# 238_power_measure.net
KiCad netlist of a schematic drawn in EAGLE
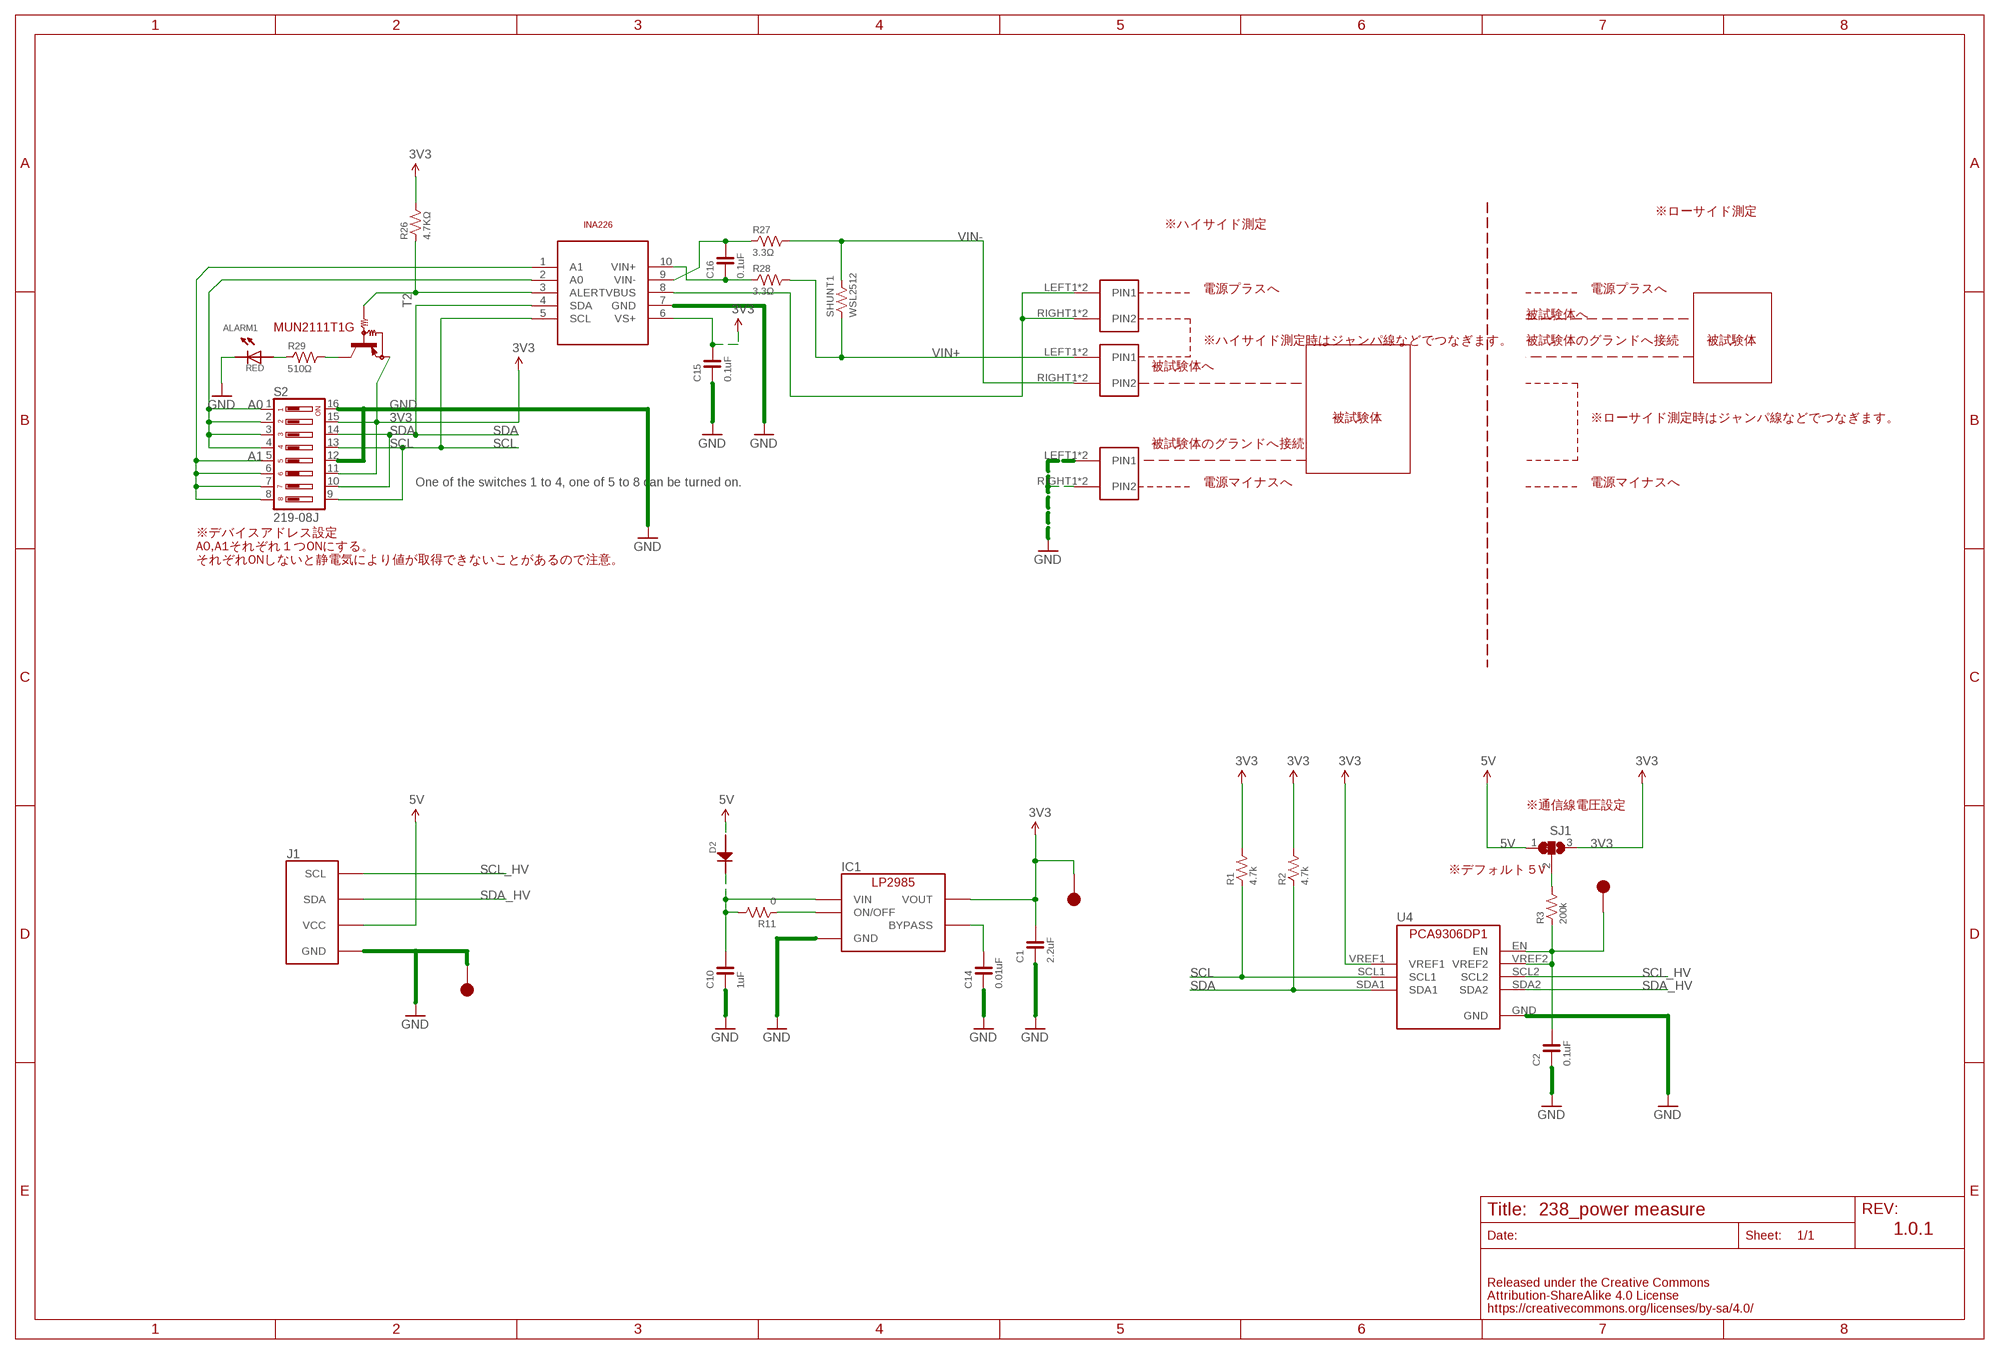
[diagram p0: schematic, sheet 1]

(export (version "E")
  (design (tool "Eeschema 10.0.6"))
  (components
    (comp (ref "ALARM1")
      (value "RED")
      (footprint "eagle-import:0603")
      (libsource (lib "eagle-import") (part "LED-0603"))
    )
    (comp (ref "C1")
      (value "2.2uF")
      (footprint "eagle-import:0603")
      (libsource (lib "eagle-import") (part "CAPACITOR-0603"))
    )
    (comp (ref "C2")
      (value "0.1uF")
      (footprint "eagle-import:0603")
      (libsource (lib "eagle-import") (part "CAPACITOR-0603"))
    )
    (comp (ref "C10")
      (value "1uF")
      (footprint "eagle-import:0603")
      (libsource (lib "eagle-import") (part "CAPACITOR-0603"))
    )
    (comp (ref "C14")
      (value "0.01uF")
      (footprint "eagle-import:0603")
      (libsource (lib "eagle-import") (part "CAPACITOR-0603"))
    )
    (comp (ref "C15")
      (value "0.1uF")
      (footprint "eagle-import:0603")
      (libsource (lib "eagle-import") (part "CAPACITOR-0603"))
    )
    (comp (ref "C16")
      (value "0.1uF")
      (footprint "eagle-import:0603")
      (libsource (lib "eagle-import") (part "CAPACITOR-0603"))
    )
    (comp (ref "D2")
      (value "1N4148")
      (footprint "eagle-import:1N4148W")
      (libsource (lib "eagle-import") (part "1N4148"))
    )
    (comp (ref "IC1")
      (value "LP2985-33")
      (footprint "eagle-import:SOT-23-5")
      (libsource (lib "eagle-import") (part "LP2985-33DBV"))
    )
    (comp (ref "J1")
      (value "FABO_BRICK_I2C-S04B-PASK-2")
      (footprint "eagle-import:FABO_BRICK_I2C_S04B-PASK-2")
      (libsource (lib "eagle-import") (part "FABO_BRICK_I2C-S04B-PASK-2"))
    )
    (comp (ref "R1")
      (value "4.7k")
      (footprint "eagle-import:0603")
      (libsource (lib "eagle-import") (part "RESISTOR-0603"))
    )
    (comp (ref "R2")
      (value "4.7k")
      (footprint "eagle-import:0603")
      (libsource (lib "eagle-import") (part "RESISTOR-0603"))
    )
    (comp (ref "R3")
      (value "200k")
      (footprint "eagle-import:0603")
      (libsource (lib "eagle-import") (part "RESISTOR-0603"))
    )
    (comp (ref "R11")
      (value "0")
      (footprint "eagle-import:0603")
      (libsource (lib "eagle-import") (part "RESISTOR-0603"))
    )
    (comp (ref "R26")
      (value "4.7KΩ")
      (footprint "eagle-import:0603")
      (libsource (lib "eagle-import") (part "RESISTOR-0603"))
    )
    (comp (ref "R27")
      (value "3.3Ω")
      (footprint "eagle-import:0603")
      (libsource (lib "eagle-import") (part "RESISTOR-0603"))
    )
    (comp (ref "R28")
      (value "3.3Ω")
      (footprint "eagle-import:0603")
      (libsource (lib "eagle-import") (part "RESISTOR-0603"))
    )
    (comp (ref "R29")
      (value "510Ω")
      (footprint "eagle-import:0603")
      (libsource (lib "eagle-import") (part "RESISTOR-0603"))
    )
    (comp (ref "S2")
      (value "219-08J")
      (footprint "eagle-import:CTS-219-08J")
      (libsource (lib "eagle-import") (part "219-08J"))
    )
    (comp (ref "SHUNT1")
      (value "WSL2512")
      (footprint "eagle-import:2512INCH")
      (libsource (lib "eagle-import") (part "WSL2512"))
    )
    (comp (ref "SJ1")
      (value "SJ2W")
      (footprint "eagle-import:SJ_2")
      (libsource (lib "eagle-import") (part "SJ2W"))
    )
    (comp (ref "T2")
      (value "MUN2111T1-PNP_DRIVER-SC59-BEC")
      (footprint "eagle-import:SC59-BEC")
      (libsource (lib "eagle-import") (part "-PNP_DRIVER-SC59-BECMUN2111T1"))
    )
    (comp (ref "TP1")
      (value "TP-15")
      (footprint "eagle-import:TP-15")
      (libsource (lib "eagle-import") (part "TP-15"))
    )
    (comp (ref "TP2")
      (value "TP-15")
      (footprint "eagle-import:TP-15")
      (libsource (lib "eagle-import") (part "TP-15"))
    )
    (comp (ref "TP5")
      (value "TP-15")
      (footprint "eagle-import:TP-15")
      (libsource (lib "eagle-import") (part "TP-15"))
    )
    (comp (ref "U$23")
      (value "ML-1400-S1")
      (footprint "eagle-import:ML-1400-S1")
      (libsource (lib "eagle-import") (part "ML-1400-S1"))
    )
    (comp (ref "U$24")
      (value "ML-1400-S1")
      (footprint "eagle-import:ML-1400-S1")
      (libsource (lib "eagle-import") (part "ML-1400-S1"))
    )
    (comp (ref "U$25")
      (value "ML-1400-S1")
      (footprint "eagle-import:ML-1400-S1")
      (libsource (lib "eagle-import") (part "ML-1400-S1"))
    )
    (comp (ref "U3")
      (value "TI-INA226")
      (footprint "eagle-import:TI-INA226")
      (libsource (lib "eagle-import") (part "TI-INA226"))
    )
    (comp (ref "U4")
      (value "PCA9306DP1")
      (footprint "eagle-import:TSSOP8")
      (libsource (lib "eagle-import") (part "PCA9306DP1"))
    )
  )
  (nets
    (net (code "1") (name "/A0") (class "Default")
      (node (ref "S2") (pin "1") (pinfunction "1_1") (pintype "passive"))
      (node (ref "S2") (pin "2") (pinfunction "2_2") (pintype "passive"))
      (node (ref "S2") (pin "3") (pinfunction "3_3") (pintype "passive"))
      (node (ref "S2") (pin "4") (pinfunction "4_4") (pintype "passive"))
      (node (ref "U3") (pin "2") (pinfunction "A0_2") (pintype "bidirectional"))
    )
    (net (code "2") (name "/A1") (class "Default")
      (node (ref "S2") (pin "5") (pinfunction "5_5") (pintype "passive"))
      (node (ref "S2") (pin "6") (pinfunction "6_6") (pintype "passive"))
      (node (ref "S2") (pin "7") (pinfunction "7_7") (pintype "passive"))
      (node (ref "S2") (pin "8") (pinfunction "8_8") (pintype "passive"))
      (node (ref "U3") (pin "1") (pinfunction "A1_1") (pintype "bidirectional"))
    )
    (net (code "3") (name "/SCL") (class "Default")
      (node (ref "R1") (pin "1") (pinfunction "1_1") (pintype "bidirectional"))
      (node (ref "S2") (pin "13") (pinfunction "13_13") (pintype "passive"))
      (node (ref "S2") (pin "9") (pinfunction "9_9") (pintype "passive"))
      (node (ref "U3") (pin "5") (pinfunction "SCL_5") (pintype "bidirectional"))
      (node (ref "U4") (pin "SCL1") (pinfunction "SCL1_SCL1") (pintype "bidirectional"))
    )
    (net (code "4") (name "/SCL_HV") (class "Default")
      (node (ref "J1") (pin "SCL") (pinfunction "SCL_SCL") (pintype "bidirectional"))
      (node (ref "U4") (pin "SCL2") (pinfunction "SCL2_SCL2") (pintype "bidirectional"))
    )
    (net (code "5") (name "/SDA") (class "Default")
      (node (ref "R2") (pin "1") (pinfunction "1_1") (pintype "bidirectional"))
      (node (ref "S2") (pin "10") (pinfunction "10_10") (pintype "passive"))
      (node (ref "S2") (pin "14") (pinfunction "14_14") (pintype "passive"))
      (node (ref "U3") (pin "4") (pinfunction "SDA_4") (pintype "bidirectional"))
      (node (ref "U4") (pin "SDA1") (pinfunction "SDA1_SDA1") (pintype "bidirectional"))
    )
    (net (code "6") (name "/SDA_HV") (class "Default")
      (node (ref "J1") (pin "SDA") (pinfunction "SDA_SDA") (pintype "bidirectional"))
      (node (ref "U4") (pin "SDA2") (pinfunction "SDA2_SDA2") (pintype "bidirectional"))
    )
    (net (code "7") (name "/VIN+") (class "Default")
      (node (ref "R28") (pin "2") (pinfunction "2_2") (pintype "bidirectional"))
      (node (ref "SHUNT1") (pin "P$1") (pinfunction "1_P$1") (pintype "bidirectional"))
      (node (ref "U$24") (pin "LEFT1") (pinfunction "PIN1_LEFT1") (pintype "bidirectional"))
      (node (ref "U$24") (pin "LEFT2") (pinfunction "PIN1_LEFT2") (pintype "bidirectional"))
    )
    (net (code "8") (name "/VIN-") (class "Default")
      (node (ref "R27") (pin "2") (pinfunction "2_2") (pintype "bidirectional"))
      (node (ref "SHUNT1") (pin "P$2") (pinfunction "2_P$2") (pintype "bidirectional"))
      (node (ref "U$24") (pin "RIGHT1") (pinfunction "PIN2_RIGHT1") (pintype "bidirectional"))
      (node (ref "U$24") (pin "RIGHT2") (pinfunction "PIN2_RIGHT2") (pintype "bidirectional"))
    )
    (net (code "9") (name "3V3") (class "Default")
      (node (ref "C1") (pin "2") (pinfunction "2_2") (pintype "passive"))
      (node (ref "C15") (pin "2") (pinfunction "2_2") (pintype "passive"))
      (node (ref "IC1") (pin "5") (pinfunction "VOUT_5") (pintype "output"))
      (node (ref "R1") (pin "2") (pinfunction "2_2") (pintype "bidirectional"))
      (node (ref "R2") (pin "2") (pinfunction "2_2") (pintype "bidirectional"))
      (node (ref "R26") (pin "2") (pinfunction "2_2") (pintype "bidirectional"))
      (node (ref "S2") (pin "11") (pinfunction "11_11") (pintype "passive"))
      (node (ref "S2") (pin "15") (pinfunction "15_15") (pintype "passive"))
      (node (ref "SJ1") (pin "3") (pinfunction "3_3") (pintype "passive"))
      (node (ref "T2") (pin "E") (pinfunction "E_E") (pintype "passive"))
      (node (ref "TP5") (pin "1") (pinfunction "1_1") (pintype "bidirectional"))
      (node (ref "U3") (pin "6") (pinfunction "VS+_6") (pintype "bidirectional"))
      (node (ref "U4") (pin "VREF1") (pinfunction "VREF1_VREF1") (pintype "bidirectional"))
    )
    (net (code "10") (name "5V") (class "Default")
      (node (ref "D2") (pin "ANODE") (pinfunction "ANODE_ANODE") (pintype "bidirectional"))
      (node (ref "J1") (pin "VCC") (pinfunction "VCC_VCC") (pintype "bidirectional"))
      (node (ref "SJ1") (pin "1") (pinfunction "1_1") (pintype "passive"))
    )
    (net (code "11") (name "GND") (class "Default")
      (node (ref "ALARM1") (pin "CATHODE") (pinfunction "CATHODE_CATHODE") (pintype "passive"))
      (node (ref "C1") (pin "1") (pinfunction "1_1") (pintype "passive"))
      (node (ref "C10") (pin "1") (pinfunction "1_1") (pintype "passive"))
      (node (ref "C14") (pin "1") (pinfunction "1_1") (pintype "passive"))
      (node (ref "C15") (pin "1") (pinfunction "1_1") (pintype "passive"))
      (node (ref "C2") (pin "1") (pinfunction "1_1") (pintype "passive"))
      (node (ref "IC1") (pin "2") (pinfunction "GND_2") (pintype "power_in"))
      (node (ref "J1") (pin "GND") (pinfunction "GND_GND") (pintype "bidirectional"))
      (node (ref "S2") (pin "12") (pinfunction "12_12") (pintype "passive"))
      (node (ref "S2") (pin "16") (pinfunction "16_16") (pintype "passive"))
      (node (ref "TP1") (pin "1") (pinfunction "1_1") (pintype "bidirectional"))
      (node (ref "U$25") (pin "LEFT1") (pinfunction "PIN1_LEFT1") (pintype "bidirectional"))
      (node (ref "U$25") (pin "LEFT2") (pinfunction "PIN1_LEFT2") (pintype "bidirectional"))
      (node (ref "U$25") (pin "RIGHT1") (pinfunction "PIN2_RIGHT1") (pintype "bidirectional"))
      (node (ref "U$25") (pin "RIGHT2") (pinfunction "PIN2_RIGHT2") (pintype "bidirectional"))
      (node (ref "U3") (pin "7") (pinfunction "GND_7") (pintype "bidirectional"))
      (node (ref "U4") (pin "GND") (pinfunction "GND_GND") (pintype "bidirectional"))
    )
    (net (code "12") (name "Net-(ALARM1-PadANODE)") (class "Default")
      (node (ref "ALARM1") (pin "ANODE") (pinfunction "ANODE_ANODE") (pintype "passive"))
      (node (ref "R29") (pin "1") (pinfunction "1_1") (pintype "bidirectional"))
    )
    (net (code "13") (name "Net-(C2-Pad2)") (class "Default")
      (node (ref "C2") (pin "2") (pinfunction "2_2") (pintype "passive"))
      (node (ref "R3") (pin "1") (pinfunction "1_1") (pintype "bidirectional"))
      (node (ref "TP2") (pin "1") (pinfunction "1_1") (pintype "bidirectional"))
      (node (ref "U4") (pin "EN") (pinfunction "EN_EN") (pintype "bidirectional"))
      (node (ref "U4") (pin "VREF2") (pinfunction "VREF2_VREF2") (pintype "bidirectional"))
    )
    (net (code "14") (name "Net-(IC1-BYPASS)") (class "Default")
      (node (ref "C14") (pin "2") (pinfunction "2_2") (pintype "passive"))
      (node (ref "IC1") (pin "4") (pinfunction "BYPASS_4") (pintype "bidirectional"))
    )
    (net (code "15") (name "Net-(IC1-ON{slash}OFF)") (class "Default")
      (node (ref "IC1") (pin "3") (pinfunction "ON/OFF_3") (pintype "input"))
      (node (ref "R11") (pin "1") (pinfunction "1_1") (pintype "bidirectional"))
    )
    (net (code "16") (name "Net-(IC1-VIN)") (class "Default")
      (node (ref "C10") (pin "2") (pinfunction "2_2") (pintype "passive"))
      (node (ref "D2") (pin "CATHODE") (pinfunction "CATHODE_CATHODE") (pintype "bidirectional"))
      (node (ref "IC1") (pin "1") (pinfunction "VIN_1") (pintype "input"))
      (node (ref "R11") (pin "2") (pinfunction "2_2") (pintype "bidirectional"))
    )
    (net (code "17") (name "Net-(R3-Pad2)") (class "Default")
      (node (ref "R3") (pin "2") (pinfunction "2_2") (pintype "bidirectional"))
      (node (ref "SJ1") (pin "2") (pinfunction "2_2") (pintype "passive"))
    )
    (net (code "18") (name "Net-(R29-Pad2)") (class "Default")
      (node (ref "R29") (pin "2") (pinfunction "2_2") (pintype "bidirectional"))
      (node (ref "T2") (pin "C") (pinfunction "C_C") (pintype "passive"))
    )
    (net (code "19") (name "Net-(U3-ALERT)") (class "Default")
      (node (ref "R26") (pin "1") (pinfunction "1_1") (pintype "bidirectional"))
      (node (ref "T2") (pin "B") (pinfunction "B_B") (pintype "passive"))
      (node (ref "U3") (pin "3") (pinfunction "ALERT_3") (pintype "bidirectional"))
    )
    (net (code "20") (name "Net-(U3-VBUS)") (class "Default")
      (node (ref "U$23") (pin "LEFT1") (pinfunction "PIN1_LEFT1") (pintype "bidirectional"))
      (node (ref "U$23") (pin "LEFT2") (pinfunction "PIN1_LEFT2") (pintype "bidirectional"))
      (node (ref "U$23") (pin "RIGHT1") (pinfunction "PIN2_RIGHT1") (pintype "bidirectional"))
      (node (ref "U$23") (pin "RIGHT2") (pinfunction "PIN2_RIGHT2") (pintype "bidirectional"))
      (node (ref "U3") (pin "8") (pinfunction "VBUS_8") (pintype "bidirectional"))
    )
    (net (code "21") (name "Net-(U3-VIN+)") (class "Default")
      (node (ref "C16") (pin "1") (pinfunction "1_1") (pintype "passive"))
      (node (ref "R28") (pin "1") (pinfunction "1_1") (pintype "bidirectional"))
      (node (ref "U3") (pin "10") (pinfunction "VIN+_10") (pintype "bidirectional"))
    )
    (net (code "22") (name "Net-(U3-VIN-)") (class "Default")
      (node (ref "C16") (pin "2") (pinfunction "2_2") (pintype "passive"))
      (node (ref "R27") (pin "1") (pinfunction "1_1") (pintype "bidirectional"))
      (node (ref "U3") (pin "9") (pinfunction "VIN-_9") (pintype "bidirectional"))
    )
  )
)
